# QUAD_BUCK.net
KiCad netlist of a schematic drawn in Altium Designer
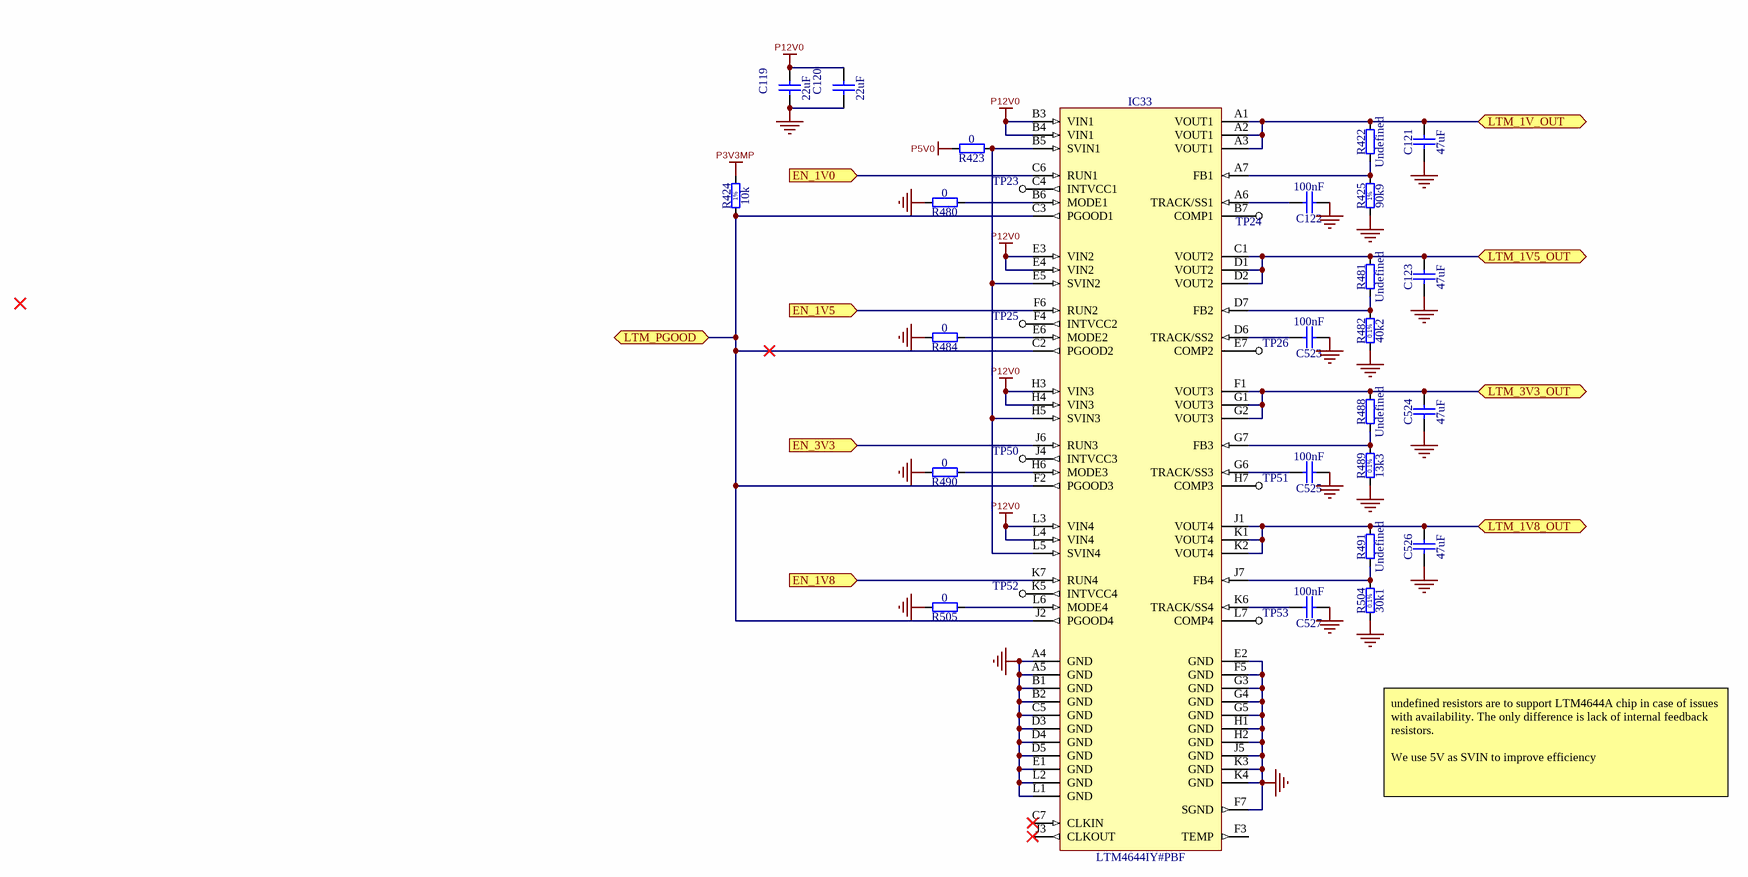
[diagram p0: QUAD_BUCK.SchDoc]

(export (version "E")
  (design (tool "Eeschema 10.0.6"))
  (components
    (comp (ref "C119")
      (value "22uF")
      (footprint "CAPC2012X135N")
      (description "Non-polarised capacitor")
      (fields
        (field (name "MANUFACTURER PART NUMBER") "CC0805_22UF_16V_10%_X5R")
        (field (name "MANUFACTURER") "GENERIC")
        (field (name "AUTHOR") "CERN DEM JLC")
      )
      (libsource (lib "Capacitors") (part "Capacitor - non polarized"))
    )
    (comp (ref "C120")
      (value "22uF")
      (footprint "CAPC2012X135N")
      (description "Non-polarised capacitor")
      (fields
        (field (name "MANUFACTURER PART NUMBER") "CC0805_22UF_16V_10%_X5R")
        (field (name "MANUFACTURER") "GENERIC")
        (field (name "AUTHOR") "CERN DEM JLC")
      )
      (libsource (lib "Capacitors") (part "Capacitor - non polarized"))
    )
    (comp (ref "C121")
      (value "47uF")
      (footprint "CAPC2012X140N")
      (description "Non-polarised capacitor")
      (fields
        (field (name "MANUFACTURER PART NUMBER") "CC0805_47UF_6.3V_20%_X5R")
        (field (name "MANUFACTURER") "GENERIC")
        (field (name "AUTHOR") "CERN DEM JLC")
      )
      (libsource (lib "Capacitors") (part "Capacitor - non polarized"))
    )
    (comp (ref "C122")
      (value "100nF")
      (footprint "CAPC1005X55N")
      (description "Non-polarised capacitor")
      (fields
        (field (name "PART NUMBER") "CC0402_100NF_16V_10%_X5R")
        (field (name "VOLTAGE") "16V")
        (field (name "AUTHOR") "CERN DEM JLC")
      )
      (libsource (lib "Capacitors") (part "Capacitor - non polarized"))
    )
    (comp (ref "C123")
      (value "47uF")
      (footprint "CAPC2012X140N")
      (description "Non-polarised capacitor")
      (fields
        (field (name "MANUFACTURER PART NUMBER") "CC0805_47UF_6.3V_20%_X5R")
        (field (name "MANUFACTURER") "GENERIC")
        (field (name "AUTHOR") "CERN DEM JLC")
      )
      (libsource (lib "Capacitors") (part "Capacitor - non polarized"))
    )
    (comp (ref "C523")
      (value "100nF")
      (footprint "CAPC1005X55N")
      (description "Non-polarised capacitor")
      (fields
        (field (name "PART NUMBER") "CC0402_100NF_16V_10%_X5R")
        (field (name "VOLTAGE") "16V")
        (field (name "AUTHOR") "CERN DEM JLC")
      )
      (libsource (lib "Capacitors") (part "Capacitor - non polarized"))
    )
    (comp (ref "C524")
      (value "47uF")
      (footprint "CAPC2012X140N")
      (description "Non-polarised capacitor")
      (fields
        (field (name "MANUFACTURER PART NUMBER") "CC0805_47UF_6.3V_20%_X5R")
        (field (name "MANUFACTURER") "GENERIC")
        (field (name "AUTHOR") "CERN DEM JLC")
      )
      (libsource (lib "Capacitors") (part "Capacitor - non polarized"))
    )
    (comp (ref "C525")
      (value "100nF")
      (footprint "CAPC1005X55N")
      (description "Non-polarised capacitor")
      (fields
        (field (name "PART NUMBER") "CC0402_100NF_16V_10%_X5R")
        (field (name "VOLTAGE") "16V")
        (field (name "AUTHOR") "CERN DEM JLC")
      )
      (libsource (lib "Capacitors") (part "Capacitor - non polarized"))
    )
    (comp (ref "C526")
      (value "47uF")
      (footprint "CAPC2012X140N")
      (description "Non-polarised capacitor")
      (fields
        (field (name "MANUFACTURER PART NUMBER") "CC0805_47UF_6.3V_20%_X5R")
        (field (name "MANUFACTURER") "GENERIC")
        (field (name "AUTHOR") "CERN DEM JLC")
      )
      (libsource (lib "Capacitors") (part "Capacitor - non polarized"))
    )
    (comp (ref "C527")
      (value "100nF")
      (footprint "CAPC1005X55N")
      (description "Non-polarised capacitor")
      (fields
        (field (name "PART NUMBER") "CC0402_100NF_16V_10%_X5R")
        (field (name "VOLTAGE") "16V")
        (field (name "AUTHOR") "CERN DEM JLC")
      )
      (libsource (lib "Capacitors") (part "Capacitor - non polarized"))
    )
    (comp (ref "IC33")
      (value "LTM4644IY#PBF")
      (footprint "BGA77C127P7X11_900X1500X521")
      (description "Quad DC/DC µModule Regulator with Configurable 4A Output Array")
      (fields (field (name "MANUFACTURER") "LINEAR TECHNOLOGY") (field (name "AUTHOR") "CERN DEM JLC"))
      (libsource (lib "ICs And Semiconductors") (part "LTM4644"))
    )
    (comp (ref "R422")
      (value "Undefined")
      (footprint "RESC1608X55N")
      (description "Resistor")
      (fields (field (name "PART NUMBER") "R0603_NO-VALUE") (field (name "AUTHOR") "CERN DEM JLC"))
      (libsource (lib "Resistors") (part "Resistor"))
    )
    (comp (ref "R423")
      (value "0")
      (footprint "RESC1005X40N")
      (description "Resistor")
      (fields
        (field (name "MANUFACTURER PART NUMBER") "R0402_0R_JUMPER")
        (field (name "MANUFACTURER") "GENERIC")
        (field (name "AUTHOR") "CERN DEM JLC")
      )
      (libsource (lib "Resistors") (part "Resistor"))
    )
    (comp (ref "R424")
      (value "10k")
      (footprint "RESC1005X40N")
      (description "Resistor - 1%")
      (fields
        (field (name "MANUFACTURER PART NUMBER") "R0402_10K_1%_0.0625W_100PPM")
        (field (name "MANUFACTURER") "GENERIC")
        (field (name "AUTHOR") "CERN DEM JLC")
      )
      (libsource (lib "Resistors") (part "Resistor - 1%"))
    )
    (comp (ref "R425")
      (value "90k9")
      (footprint "RESC1608X55N")
      (description "Resistor - 1%")
      (fields
        (field (name "PART NUMBER") "R0603_90K9_1%_0.1W_100PPM")
        (field (name "POWER") "0.1W")
        (field (name "AUTHOR") "CERN DEM JLC")
      )
      (libsource (lib "Resistors") (part "Resistor - 1%"))
    )
    (comp (ref "R480")
      (value "0")
      (footprint "RESC1005X40N")
      (description "Resistor")
      (fields
        (field (name "MANUFACTURER PART NUMBER") "R0402_0R_JUMPER")
        (field (name "MANUFACTURER") "GENERIC")
        (field (name "AUTHOR") "CERN DEM JLC")
      )
      (libsource (lib "Resistors") (part "Resistor"))
    )
    (comp (ref "R481")
      (value "Undefined")
      (footprint "RESC1608X55N")
      (description "Resistor")
      (fields (field (name "PART NUMBER") "R0603_NO-VALUE") (field (name "AUTHOR") "CERN DEM JLC"))
      (libsource (lib "Resistors") (part "Resistor"))
    )
    (comp (ref "R482")
      (value "40k2")
      (footprint "RESC1608X55N")
      (description "Resistor - 0.1%")
      (fields
        (field (name "PART NUMBER") "R0603_40K2_0.1%_0.063W_10PPM")
        (field (name "POWER") "0.063W")
        (field (name "AUTHOR") "CERN DEM JLC")
      )
      (libsource (lib "Resistors") (part "Resistor - 0.1%"))
    )
    (comp (ref "R484")
      (value "0")
      (footprint "RESC1005X40N")
      (description "Resistor")
      (fields
        (field (name "MANUFACTURER PART NUMBER") "R0402_0R_JUMPER")
        (field (name "MANUFACTURER") "GENERIC")
        (field (name "AUTHOR") "CERN DEM JLC")
      )
      (libsource (lib "Resistors") (part "Resistor"))
    )
    (comp (ref "R488")
      (value "Undefined")
      (footprint "RESC1608X55N")
      (description "Resistor")
      (fields (field (name "PART NUMBER") "R0603_NO-VALUE") (field (name "AUTHOR") "CERN DEM JLC"))
      (libsource (lib "Resistors") (part "Resistor"))
    )
    (comp (ref "R489")
      (value "13k3")
      (footprint "RESC1608X55N")
      (description "Resistor - 0.1%")
      (fields
        (field (name "PART NUMBER") "R0603_13K3_0.1%_0.063W_10PPM")
        (field (name "POWER") "0.063W")
        (field (name "AUTHOR") "CERN DEM JLC")
      )
      (libsource (lib "Resistors") (part "Resistor - 0.1%"))
    )
    (comp (ref "R490")
      (value "0")
      (footprint "RESC1005X40N")
      (description "Resistor")
      (fields
        (field (name "MANUFACTURER PART NUMBER") "R0402_0R_JUMPER")
        (field (name "MANUFACTURER") "GENERIC")
        (field (name "AUTHOR") "CERN DEM JLC")
      )
      (libsource (lib "Resistors") (part "Resistor"))
    )
    (comp (ref "R491")
      (value "Undefined")
      (footprint "RESC1608X55N")
      (description "Resistor")
      (fields (field (name "PART NUMBER") "R0603_NO-VALUE") (field (name "AUTHOR") "CERN DEM JLC"))
      (libsource (lib "Resistors") (part "Resistor"))
    )
    (comp (ref "R504")
      (value "30k1")
      (footprint "RESC1608X55N")
      (description "Resistor - 0.1%")
      (fields
        (field (name "PART NUMBER") "R0603_30K1_0.1%_0.063W_10PPM")
        (field (name "POWER") "0.063W")
        (field (name "AUTHOR") "CERN DEM JLC")
      )
      (libsource (lib "Resistors") (part "Resistor - 0.1%"))
    )
    (comp (ref "R505")
      (value "0")
      (footprint "RESC1005X40N")
      (description "Resistor")
      (fields
        (field (name "MANUFACTURER PART NUMBER") "R0402_0R_JUMPER")
        (field (name "MANUFACTURER") "GENERIC")
        (field (name "AUTHOR") "CERN DEM JLC")
      )
      (libsource (lib "Resistors") (part "Resistor"))
    )
    (comp (ref "TP23")
      (value "TP")
      (footprint "TP")
      (description "Testpoint")
      (libsource (lib "LIBRARY_SCH") (part "TP"))
    )
    (comp (ref "TP24")
      (value "TP")
      (footprint "TP")
      (description "Testpoint")
      (libsource (lib "LIBRARY_SCH") (part "TP"))
    )
    (comp (ref "TP25")
      (value "TP")
      (footprint "TP")
      (description "Testpoint")
      (libsource (lib "LIBRARY_SCH") (part "TP"))
    )
    (comp (ref "TP26")
      (value "TP")
      (footprint "TP")
      (description "Testpoint")
      (libsource (lib "LIBRARY_SCH") (part "TP"))
    )
    (comp (ref "TP50")
      (value "TP")
      (footprint "TP")
      (description "Testpoint")
      (libsource (lib "LIBRARY_SCH") (part "TP"))
    )
    (comp (ref "TP51")
      (value "TP")
      (footprint "TP")
      (description "Testpoint")
      (libsource (lib "LIBRARY_SCH") (part "TP"))
    )
    (comp (ref "TP52")
      (value "TP")
      (footprint "TP")
      (description "Testpoint")
      (libsource (lib "LIBRARY_SCH") (part "TP"))
    )
    (comp (ref "TP53")
      (value "TP")
      (footprint "TP")
      (description "Testpoint")
      (libsource (lib "LIBRARY_SCH") (part "TP"))
    )
  )
  (nets
    (net (code "1") (name "/EN_1V0") (class "Default")
      (node (ref "IC33") (pin "C6") (pinfunction "RUN1_C6") (pintype "input"))
    )
    (net (code "2") (name "/EN_1V5") (class "Default")
      (node (ref "IC33") (pin "F6") (pinfunction "RUN2_F6") (pintype "input"))
    )
    (net (code "3") (name "/EN_1V8") (class "Default")
      (node (ref "IC33") (pin "K7") (pinfunction "RUN4_K7") (pintype "input"))
    )
    (net (code "4") (name "/EN_3V3") (class "Default")
      (node (ref "IC33") (pin "J6") (pinfunction "RUN3_J6") (pintype "input"))
    )
    (net (code "5") (name "/LTM_1V5_OUT") (class "Default")
      (node (ref "C123") (pin "2") (pinfunction "2_2") (pintype "passive"))
      (node (ref "IC33") (pin "C1") (pinfunction "VOUT2_C1") (pintype "power_in"))
      (node (ref "IC33") (pin "D1") (pinfunction "VOUT2_D1") (pintype "power_in"))
      (node (ref "IC33") (pin "D2") (pinfunction "VOUT2_D2") (pintype "power_in"))
      (node (ref "R481") (pin "2") (pinfunction "2_2") (pintype "passive"))
    )
    (net (code "6") (name "/LTM_1V8_OUT") (class "Default")
      (node (ref "C526") (pin "2") (pinfunction "2_2") (pintype "passive"))
      (node (ref "IC33") (pin "J1") (pinfunction "VOUT4_J1") (pintype "power_in"))
      (node (ref "IC33") (pin "K1") (pinfunction "VOUT4_K1") (pintype "power_in"))
      (node (ref "IC33") (pin "K2") (pinfunction "VOUT4_K2") (pintype "power_in"))
      (node (ref "R491") (pin "2") (pinfunction "2_2") (pintype "passive"))
    )
    (net (code "7") (name "/LTM_1V_OUT") (class "Default")
      (node (ref "C121") (pin "2") (pinfunction "2_2") (pintype "passive"))
      (node (ref "IC33") (pin "A1") (pinfunction "VOUT1_A1") (pintype "power_in"))
      (node (ref "IC33") (pin "A2") (pinfunction "VOUT1_A2") (pintype "power_in"))
      (node (ref "IC33") (pin "A3") (pinfunction "VOUT1_A3") (pintype "power_in"))
      (node (ref "R422") (pin "2") (pinfunction "2_2") (pintype "passive"))
    )
    (net (code "8") (name "/LTM_3V3_OUT") (class "Default")
      (node (ref "C524") (pin "2") (pinfunction "2_2") (pintype "passive"))
      (node (ref "IC33") (pin "F1") (pinfunction "VOUT3_F1") (pintype "power_in"))
      (node (ref "IC33") (pin "G1") (pinfunction "VOUT3_G1") (pintype "power_in"))
      (node (ref "IC33") (pin "G2") (pinfunction "VOUT3_G2") (pintype "power_in"))
      (node (ref "R488") (pin "2") (pinfunction "2_2") (pintype "passive"))
    )
    (net (code "9") (name "/LTM_PGOOD") (class "Default")
      (node (ref "IC33") (pin "C2") (pinfunction "PGOOD2_C2") (pintype "output"))
      (node (ref "IC33") (pin "C3") (pinfunction "PGOOD1_C3") (pintype "output"))
      (node (ref "IC33") (pin "F2") (pinfunction "PGOOD3_F2") (pintype "output"))
      (node (ref "IC33") (pin "J2") (pinfunction "PGOOD4_J2") (pintype "output"))
      (node (ref "R424") (pin "1") (pinfunction "1_1") (pintype "passive"))
    )
    (net (code "10") (name "GND") (class "Default")
      (node (ref "C119") (pin "1") (pinfunction "1_1") (pintype "passive"))
      (node (ref "C120") (pin "1") (pinfunction "1_1") (pintype "passive"))
      (node (ref "C121") (pin "1") (pinfunction "1_1") (pintype "passive"))
      (node (ref "C122") (pin "1") (pinfunction "1_1") (pintype "passive"))
      (node (ref "C123") (pin "1") (pinfunction "1_1") (pintype "passive"))
      (node (ref "C523") (pin "1") (pinfunction "1_1") (pintype "passive"))
      (node (ref "C524") (pin "1") (pinfunction "1_1") (pintype "passive"))
      (node (ref "C525") (pin "1") (pinfunction "1_1") (pintype "passive"))
      (node (ref "C526") (pin "1") (pinfunction "1_1") (pintype "passive"))
      (node (ref "C527") (pin "1") (pinfunction "1_1") (pintype "passive"))
      (node (ref "IC33") (pin "A4") (pinfunction "GND_A4") (pintype "power_in"))
      (node (ref "IC33") (pin "A5") (pinfunction "GND_A5") (pintype "power_in"))
      (node (ref "IC33") (pin "B1") (pinfunction "GND_B1") (pintype "power_in"))
      (node (ref "IC33") (pin "B2") (pinfunction "GND_B2") (pintype "power_in"))
      (node (ref "IC33") (pin "C5") (pinfunction "GND_C5") (pintype "power_in"))
      (node (ref "IC33") (pin "D3") (pinfunction "GND_D3") (pintype "power_in"))
      (node (ref "IC33") (pin "D4") (pinfunction "GND_D4") (pintype "power_in"))
      (node (ref "IC33") (pin "D5") (pinfunction "GND_D5") (pintype "power_in"))
      (node (ref "IC33") (pin "E1") (pinfunction "GND_E1") (pintype "power_in"))
      (node (ref "IC33") (pin "E2") (pinfunction "GND_E2") (pintype "power_in"))
      (node (ref "IC33") (pin "F5") (pinfunction "GND_F5") (pintype "power_in"))
      (node (ref "IC33") (pin "F7") (pinfunction "SGND_F7") (pintype "output"))
      (node (ref "IC33") (pin "G3") (pinfunction "GND_G3") (pintype "power_in"))
      (node (ref "IC33") (pin "G4") (pinfunction "GND_G4") (pintype "power_in"))
      (node (ref "IC33") (pin "G5") (pinfunction "GND_G5") (pintype "power_in"))
      (node (ref "IC33") (pin "H1") (pinfunction "GND_H1") (pintype "power_in"))
      (node (ref "IC33") (pin "H2") (pinfunction "GND_H2") (pintype "power_in"))
      (node (ref "IC33") (pin "J5") (pinfunction "GND_J5") (pintype "power_in"))
      (node (ref "IC33") (pin "K3") (pinfunction "GND_K3") (pintype "power_in"))
      (node (ref "IC33") (pin "K4") (pinfunction "GND_K4") (pintype "power_in"))
      (node (ref "IC33") (pin "L1") (pinfunction "GND_L1") (pintype "power_in"))
      (node (ref "IC33") (pin "L2") (pinfunction "GND_L2") (pintype "power_in"))
      (node (ref "R425") (pin "1") (pinfunction "1_1") (pintype "passive"))
      (node (ref "R480") (pin "2") (pinfunction "2_2") (pintype "passive"))
      (node (ref "R482") (pin "1") (pinfunction "1_1") (pintype "passive"))
      (node (ref "R484") (pin "2") (pinfunction "2_2") (pintype "passive"))
      (node (ref "R489") (pin "1") (pinfunction "1_1") (pintype "passive"))
      (node (ref "R490") (pin "2") (pinfunction "2_2") (pintype "passive"))
      (node (ref "R504") (pin "1") (pinfunction "1_1") (pintype "passive"))
      (node (ref "R505") (pin "2") (pinfunction "2_2") (pintype "passive"))
    )
    (net (code "11") (name "Net-(IC33-COMP1)") (class "Default")
      (node (ref "IC33") (pin "B7") (pinfunction "COMP1_B7") (pintype "passive"))
      (node (ref "TP24") (pin "1") (pintype "passive"))
    )
    (net (code "12") (name "Net-(IC33-COMP2)") (class "Default")
      (node (ref "IC33") (pin "E7") (pinfunction "COMP2_E7") (pintype "passive"))
      (node (ref "TP26") (pin "1") (pintype "passive"))
    )
    (net (code "13") (name "Net-(IC33-COMP3)") (class "Default")
      (node (ref "IC33") (pin "H7") (pinfunction "COMP3_H7") (pintype "passive"))
      (node (ref "TP51") (pin "1") (pintype "passive"))
    )
    (net (code "14") (name "Net-(IC33-COMP4)") (class "Default")
      (node (ref "IC33") (pin "L7") (pinfunction "COMP4_L7") (pintype "passive"))
      (node (ref "TP53") (pin "1") (pintype "passive"))
    )
    (net (code "15") (name "Net-(IC33-FB1)") (class "Default")
      (node (ref "IC33") (pin "A7") (pinfunction "FB1_A7") (pintype "input"))
      (node (ref "R422") (pin "1") (pinfunction "1_1") (pintype "passive"))
      (node (ref "R425") (pin "2") (pinfunction "2_2") (pintype "passive"))
    )
    (net (code "16") (name "Net-(IC33-FB2)") (class "Default")
      (node (ref "IC33") (pin "D7") (pinfunction "FB2_D7") (pintype "input"))
      (node (ref "R481") (pin "1") (pinfunction "1_1") (pintype "passive"))
      (node (ref "R482") (pin "2") (pinfunction "2_2") (pintype "passive"))
    )
    (net (code "17") (name "Net-(IC33-FB3)") (class "Default")
      (node (ref "IC33") (pin "G7") (pinfunction "FB3_G7") (pintype "input"))
      (node (ref "R488") (pin "1") (pinfunction "1_1") (pintype "passive"))
      (node (ref "R489") (pin "2") (pinfunction "2_2") (pintype "passive"))
    )
    (net (code "18") (name "Net-(IC33-FB4)") (class "Default")
      (node (ref "IC33") (pin "J7") (pinfunction "FB4_J7") (pintype "input"))
      (node (ref "R491") (pin "1") (pinfunction "1_1") (pintype "passive"))
      (node (ref "R504") (pin "2") (pinfunction "2_2") (pintype "passive"))
    )
    (net (code "19") (name "Net-(IC33-INTVCC1)") (class "Default")
      (node (ref "IC33") (pin "C4") (pinfunction "INTVCC1_C4") (pintype "output"))
      (node (ref "TP23") (pin "1") (pintype "passive"))
    )
    (net (code "20") (name "Net-(IC33-INTVCC2)") (class "Default")
      (node (ref "IC33") (pin "F4") (pinfunction "INTVCC2_F4") (pintype "output"))
      (node (ref "TP25") (pin "1") (pintype "passive"))
    )
    (net (code "21") (name "Net-(IC33-INTVCC3)") (class "Default")
      (node (ref "IC33") (pin "J4") (pinfunction "INTVCC3_J4") (pintype "output"))
      (node (ref "TP50") (pin "1") (pintype "passive"))
    )
    (net (code "22") (name "Net-(IC33-INTVCC4)") (class "Default")
      (node (ref "IC33") (pin "K5") (pinfunction "INTVCC4_K5") (pintype "output"))
      (node (ref "TP52") (pin "1") (pintype "passive"))
    )
    (net (code "23") (name "Net-(IC33-MODE1)") (class "Default")
      (node (ref "IC33") (pin "B6") (pinfunction "MODE1_B6") (pintype "input"))
      (node (ref "R480") (pin "1") (pinfunction "1_1") (pintype "passive"))
    )
    (net (code "24") (name "Net-(IC33-MODE2)") (class "Default")
      (node (ref "IC33") (pin "E6") (pinfunction "MODE2_E6") (pintype "input"))
      (node (ref "R484") (pin "1") (pinfunction "1_1") (pintype "passive"))
    )
    (net (code "25") (name "Net-(IC33-MODE3)") (class "Default")
      (node (ref "IC33") (pin "H6") (pinfunction "MODE3_H6") (pintype "input"))
      (node (ref "R490") (pin "1") (pinfunction "1_1") (pintype "passive"))
    )
    (net (code "26") (name "Net-(IC33-MODE4)") (class "Default")
      (node (ref "IC33") (pin "L6") (pinfunction "MODE4_L6") (pintype "input"))
      (node (ref "R505") (pin "1") (pinfunction "1_1") (pintype "passive"))
    )
    (net (code "27") (name "Net-(IC33-SVIN1)") (class "Default")
      (node (ref "IC33") (pin "B5") (pinfunction "SVIN1_B5") (pintype "input"))
      (node (ref "IC33") (pin "E5") (pinfunction "SVIN2_E5") (pintype "input"))
      (node (ref "IC33") (pin "H5") (pinfunction "SVIN3_H5") (pintype "input"))
      (node (ref "IC33") (pin "L5") (pinfunction "SVIN4_L5") (pintype "input"))
      (node (ref "R423") (pin "1") (pinfunction "1_1") (pintype "passive"))
    )
    (net (code "28") (name "Net-(IC33-TRACK{slash}SS1)") (class "Default")
      (node (ref "C122") (pin "2") (pinfunction "2_2") (pintype "passive"))
      (node (ref "IC33") (pin "A6") (pinfunction "TRACK/SS1_A6") (pintype "input"))
    )
    (net (code "29") (name "Net-(IC33-TRACK{slash}SS2)") (class "Default")
      (node (ref "C523") (pin "2") (pinfunction "2_2") (pintype "passive"))
      (node (ref "IC33") (pin "D6") (pinfunction "TRACK/SS2_D6") (pintype "input"))
    )
    (net (code "30") (name "Net-(IC33-TRACK{slash}SS3)") (class "Default")
      (node (ref "C525") (pin "2") (pinfunction "2_2") (pintype "passive"))
      (node (ref "IC33") (pin "G6") (pinfunction "TRACK/SS3_G6") (pintype "input"))
    )
    (net (code "31") (name "Net-(IC33-TRACK{slash}SS4)") (class "Default")
      (node (ref "C527") (pin "2") (pinfunction "2_2") (pintype "passive"))
      (node (ref "IC33") (pin "K6") (pinfunction "TRACK/SS4_K6") (pintype "input"))
    )
    (net (code "32") (name "P3V3MP") (class "Default")
      (node (ref "R424") (pin "2") (pinfunction "2_2") (pintype "passive"))
    )
    (net (code "33") (name "P5V0") (class "Default")
      (node (ref "R423") (pin "2") (pinfunction "2_2") (pintype "passive"))
    )
    (net (code "34") (name "P12V0") (class "Default")
      (node (ref "C119") (pin "2") (pinfunction "2_2") (pintype "passive"))
      (node (ref "C120") (pin "2") (pinfunction "2_2") (pintype "passive"))
      (node (ref "IC33") (pin "B3") (pinfunction "VIN1_B3") (pintype "input"))
      (node (ref "IC33") (pin "B4") (pinfunction "VIN1_B4") (pintype "input"))
      (node (ref "IC33") (pin "E3") (pinfunction "VIN2_E3") (pintype "input"))
      (node (ref "IC33") (pin "E4") (pinfunction "VIN2_E4") (pintype "input"))
      (node (ref "IC33") (pin "H3") (pinfunction "VIN3_H3") (pintype "input"))
      (node (ref "IC33") (pin "H4") (pinfunction "VIN3_H4") (pintype "input"))
      (node (ref "IC33") (pin "L3") (pinfunction "VIN4_L3") (pintype "input"))
      (node (ref "IC33") (pin "L4") (pinfunction "VIN4_L4") (pintype "input"))
    )
    (net (code "35") (name "unconnected-(IC33-CLKIN-PadC7)") (class "Default")
      (node (ref "IC33") (pin "C7") (pinfunction "CLKIN_C7") (pintype "input+no_connect"))
    )
    (net (code "36") (name "unconnected-(IC33-CLKOUT-PadJ3)") (class "Default")
      (node (ref "IC33") (pin "J3") (pinfunction "CLKOUT_J3") (pintype "output+no_connect"))
    )
    (net (code "37") (name "unconnected-(IC33-TEMP-PadF3)") (class "Default")
      (node (ref "IC33") (pin "F3") (pinfunction "TEMP_F3") (pintype "output"))
    )
  )
)
